# preamp.net
KiCad netlist of a schematic drawn in EAGLE
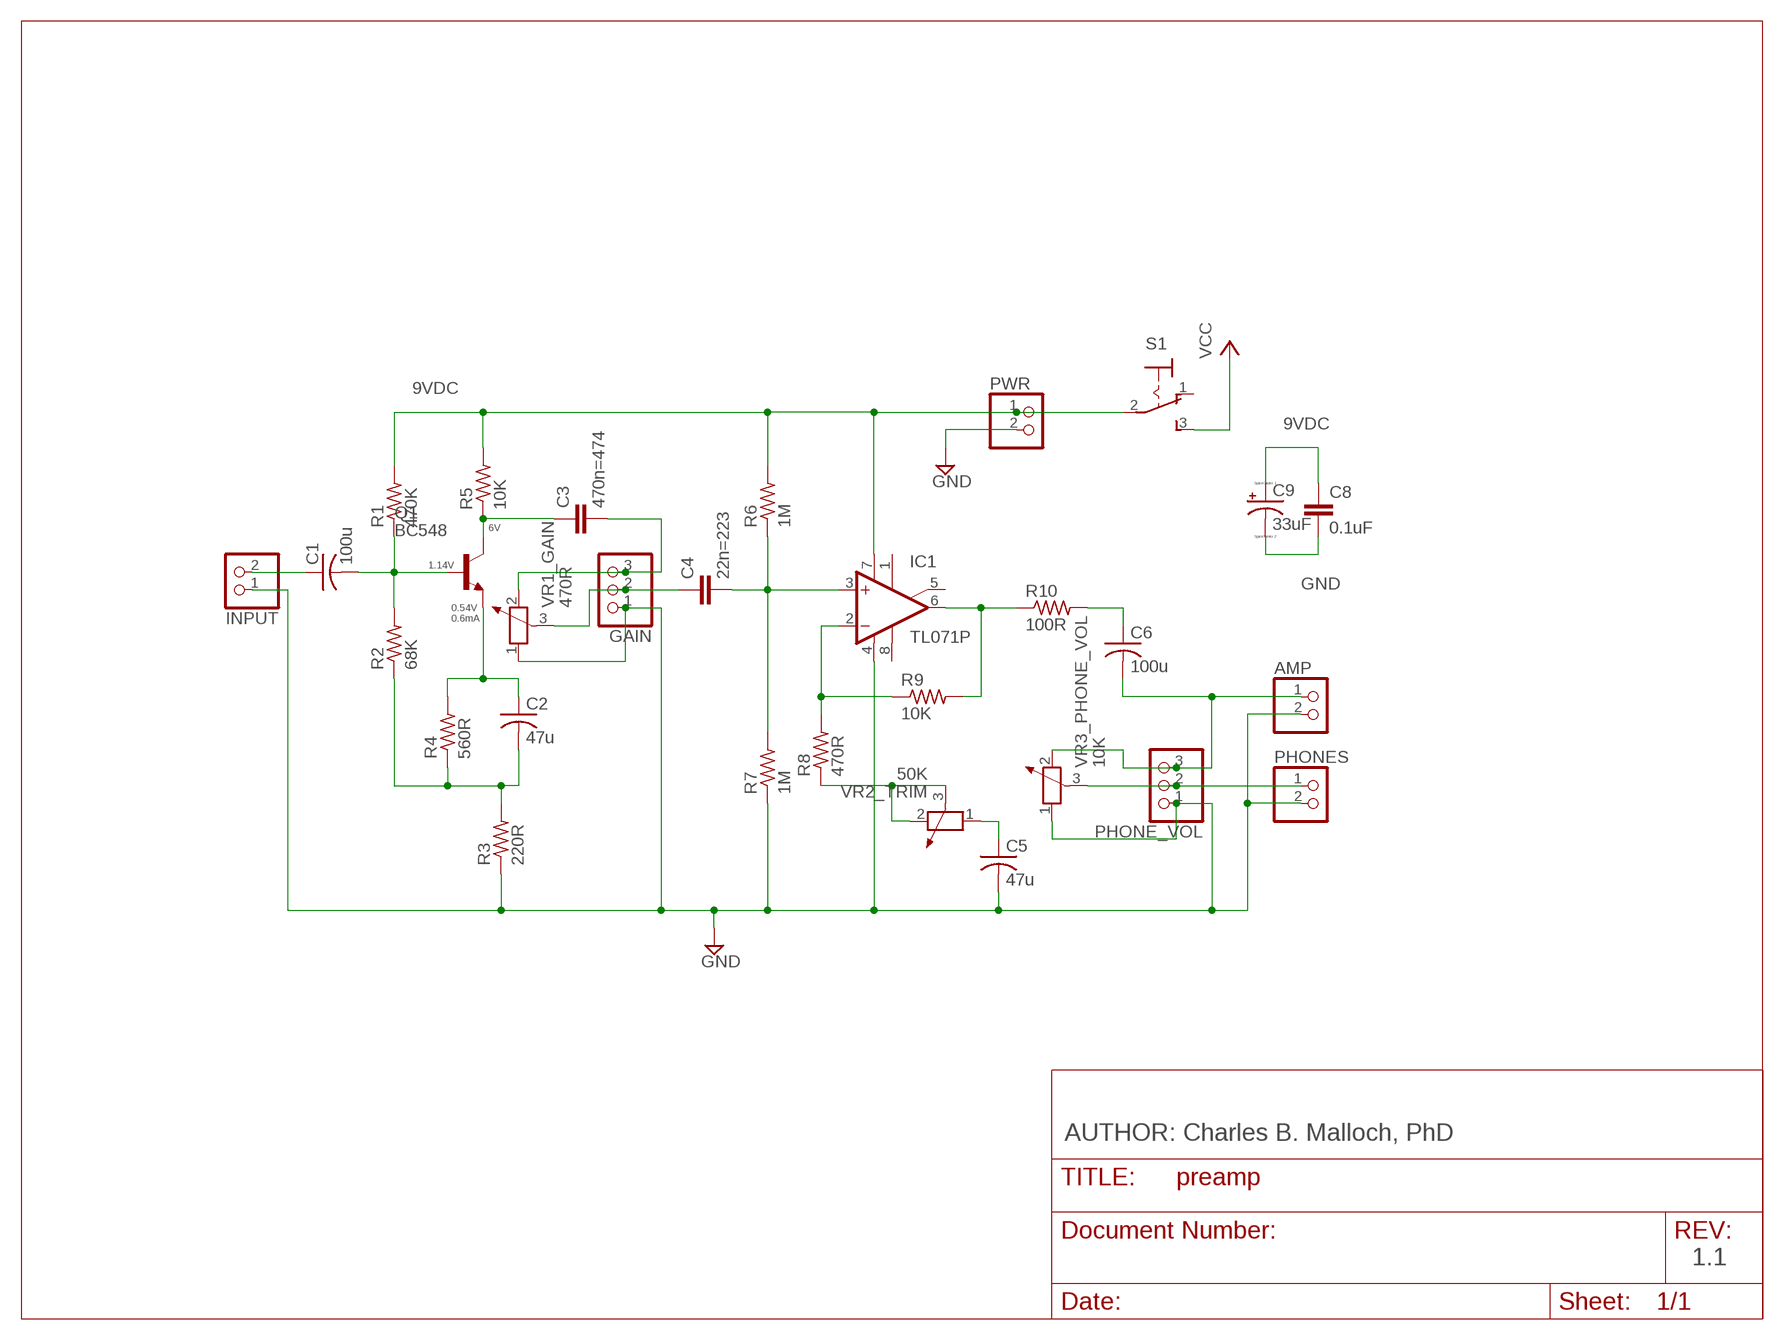
[diagram p0: schematic, sheet 1]

(export (version "E")
  (design (tool "Eeschema 10.0.6"))
  (components
    (comp (ref "AMP")
      (value "PINHD-1X2")
      (footprint "eagle-import:1X02")
      (libsource (lib "eagle-import") (part "PINHD-1X2"))
    )
    (comp (ref "C1")
      (value "100u")
      (footprint "eagle-import:C025-040X050")
      (libsource (lib "eagle-import") (part "C-US025-040X050"))
    )
    (comp (ref "C2")
      (value "47u")
      (footprint "eagle-import:C025-040X050")
      (libsource (lib "eagle-import") (part "C-US025-040X050"))
    )
    (comp (ref "C3")
      (value "470n=474")
      (footprint "eagle-import:C025-060X050")
      (libsource (lib "eagle-import") (part "C-EU025-060X050"))
    )
    (comp (ref "C4")
      (value "22n=223")
      (footprint "eagle-import:C025-060X050")
      (libsource (lib "eagle-import") (part "C-EU025-060X050"))
    )
    (comp (ref "C5")
      (value "47u")
      (footprint "eagle-import:C025-040X050")
      (libsource (lib "eagle-import") (part "C-US025-040X050"))
    )
    (comp (ref "C6")
      (value "100u")
      (footprint "eagle-import:C025-040X050")
      (libsource (lib "eagle-import") (part "C-US025-040X050"))
    )
    (comp (ref "C8")
      (value "0.1uF")
      (footprint "eagle-import:C025-030X050")
      (libsource (lib "eagle-import") (part "resistor_348_C-EU025-030X050"))
    )
    (comp (ref "C9")
      (value "33uF")
      (footprint "eagle-import:E5-6")
      (libsource (lib "eagle-import") (part "CPOL-USE5-6"))
    )
    (comp (ref "GAIN")
      (value "PINHD-1X3")
      (footprint "eagle-import:1X03")
      (libsource (lib "eagle-import") (part "PINHD-1X3"))
    )
    (comp (ref "IC1")
      (value "TL071P")
      (footprint "eagle-import:DIL08")
      (libsource (lib "eagle-import") (part "TL071P"))
    )
    (comp (ref "INPUT")
      (value "PINHD-1X2")
      (footprint "eagle-import:1X02")
      (libsource (lib "eagle-import") (part "PINHD-1X2"))
    )
    (comp (ref "PHONES")
      (value "PINHD-1X2")
      (footprint "eagle-import:1X02")
      (libsource (lib "eagle-import") (part "PINHD-1X2"))
    )
    (comp (ref "PHONE_VOL")
      (value "PINHD-1X3")
      (footprint "eagle-import:1X03")
      (libsource (lib "eagle-import") (part "PINHD-1X3"))
    )
    (comp (ref "PWR")
      (value "PINHD-1X2")
      (footprint "eagle-import:1X02")
      (libsource (lib "eagle-import") (part "PINHD-1X2"))
    )
    (comp (ref "Q1")
      (value "BC548")
      (footprint "eagle-import:TO92-EBC")
      (libsource (lib "eagle-import") (part "BC548"))
    )
    (comp (ref "R1")
      (value "470K")
      (footprint "eagle-import:0204_7")
      (libsource (lib "eagle-import") (part "R-US_0204/7"))
    )
    (comp (ref "R2")
      (value "68K")
      (footprint "eagle-import:0204_7")
      (libsource (lib "eagle-import") (part "R-US_0204/7"))
    )
    (comp (ref "R3")
      (value "220R")
      (footprint "eagle-import:0204_7")
      (libsource (lib "eagle-import") (part "R-US_0204/7"))
    )
    (comp (ref "R4")
      (value "560R")
      (footprint "eagle-import:0204_7")
      (libsource (lib "eagle-import") (part "R-US_0204/7"))
    )
    (comp (ref "R5")
      (value "10K")
      (footprint "eagle-import:0204_7")
      (libsource (lib "eagle-import") (part "R-US_0204/7"))
    )
    (comp (ref "R6")
      (value "1M")
      (footprint "eagle-import:0204_7")
      (libsource (lib "eagle-import") (part "R-US_0204/7"))
    )
    (comp (ref "R7")
      (value "1M")
      (footprint "eagle-import:0204_7")
      (libsource (lib "eagle-import") (part "R-US_0204/7"))
    )
    (comp (ref "R8")
      (value "470R")
      (footprint "eagle-import:0204_7")
      (libsource (lib "eagle-import") (part "R-US_0204/7"))
    )
    (comp (ref "R9")
      (value "10K")
      (footprint "eagle-import:0204_7")
      (libsource (lib "eagle-import") (part "R-US_0204/7"))
    )
    (comp (ref "R10")
      (value "100R")
      (footprint "eagle-import:0204_7")
      (libsource (lib "eagle-import") (part "R-US_0204/7"))
    )
    (comp (ref "S1")
      (value "320-916")
      (footprint "eagle-import:320-916")
      (libsource (lib "eagle-import") (part "320-916"))
    )
    (comp (ref "VR1_GAIN")
      (value "470R")
      (footprint "eagle-import:PT-10")
      (libsource (lib "eagle-import") (part "POTENTIOMETER_PT-10"))
    )
    (comp (ref "VR2_TRIM")
      (value "50K")
      (footprint "eagle-import:PT-10")
      (libsource (lib "eagle-import") (part "POTENTIOMETER_PT-10"))
    )
    (comp (ref "VR3_PHONE_VOL")
      (value "10K")
      (footprint "eagle-import:PT-10")
      (libsource (lib "eagle-import") (part "POTENTIOMETER_PT-10"))
    )
  )
  (nets
    (net (code "1") (name "/9VDC") (class "Default")
      (node (ref "C8") (pin "1") (pinfunction "1_1") (pintype "passive"))
      (node (ref "C9") (pin "+") (pinfunction "+_+") (pintype "passive"))
      (node (ref "IC1") (pin "7") (pinfunction "V+_7") (pintype "power_in"))
      (node (ref "PWR") (pin "1") (pinfunction "1_1") (pintype "passive"))
      (node (ref "R1") (pin "2") (pinfunction "2_2") (pintype "passive"))
      (node (ref "R5") (pin "2") (pinfunction "2_2") (pintype "passive"))
      (node (ref "R6") (pin "2") (pinfunction "2_2") (pintype "passive"))
      (node (ref "S1") (pin "2") (pinfunction "P_2") (pintype "passive"))
    )
    (net (code "2") (name "GND") (class "Default")
      (node (ref "AMP") (pin "2") (pinfunction "2_2") (pintype "passive"))
      (node (ref "C5") (pin "2") (pinfunction "2_2") (pintype "passive"))
      (node (ref "C8") (pin "2") (pinfunction "2_2") (pintype "passive"))
      (node (ref "C9") (pin "-") (pinfunction "-_-") (pintype "passive"))
      (node (ref "GAIN") (pin "1") (pinfunction "1_1") (pintype "passive"))
      (node (ref "IC1") (pin "4") (pinfunction "V-_4") (pintype "power_in"))
      (node (ref "INPUT") (pin "1") (pinfunction "1_1") (pintype "passive"))
      (node (ref "PHONES") (pin "2") (pinfunction "2_2") (pintype "passive"))
      (node (ref "PHONE_VOL") (pin "1") (pinfunction "1_1") (pintype "passive"))
      (node (ref "PWR") (pin "2") (pinfunction "2_2") (pintype "passive"))
      (node (ref "R3") (pin "1") (pinfunction "1_1") (pintype "passive"))
      (node (ref "R7") (pin "1") (pinfunction "1_1") (pintype "passive"))
      (node (ref "VR1_GAIN") (pin "1") (pinfunction "1_1") (pintype "passive"))
      (node (ref "VR3_PHONE_VOL") (pin "1") (pinfunction "1_1") (pintype "passive"))
    )
    (net (code "3") (name "Net-(AMP-Pad1)") (class "Default")
      (node (ref "AMP") (pin "1") (pinfunction "1_1") (pintype "passive"))
      (node (ref "C6") (pin "2") (pinfunction "2_2") (pintype "passive"))
      (node (ref "PHONE_VOL") (pin "3") (pinfunction "3_3") (pintype "passive"))
      (node (ref "VR3_PHONE_VOL") (pin "2") (pinfunction "2_2") (pintype "passive"))
    )
    (net (code "4") (name "Net-(C1-Pad1)") (class "Default")
      (node (ref "C1") (pin "1") (pinfunction "1_1") (pintype "passive"))
      (node (ref "INPUT") (pin "2") (pinfunction "2_2") (pintype "passive"))
    )
    (net (code "5") (name "Net-(C1-Pad2)") (class "Default")
      (node (ref "C1") (pin "2") (pinfunction "2_2") (pintype "passive"))
      (node (ref "Q1") (pin "B") (pinfunction "B_B") (pintype "passive"))
      (node (ref "R1") (pin "1") (pinfunction "1_1") (pintype "passive"))
      (node (ref "R2") (pin "2") (pinfunction "2_2") (pintype "passive"))
    )
    (net (code "6") (name "Net-(C2-Pad1)") (class "Default")
      (node (ref "C2") (pin "1") (pinfunction "1_1") (pintype "passive"))
      (node (ref "Q1") (pin "E") (pinfunction "E_E") (pintype "passive"))
      (node (ref "R4") (pin "2") (pinfunction "2_2") (pintype "passive"))
    )
    (net (code "7") (name "Net-(C2-Pad2)") (class "Default")
      (node (ref "C2") (pin "2") (pinfunction "2_2") (pintype "passive"))
      (node (ref "R2") (pin "1") (pinfunction "1_1") (pintype "passive"))
      (node (ref "R3") (pin "2") (pinfunction "2_2") (pintype "passive"))
      (node (ref "R4") (pin "1") (pinfunction "1_1") (pintype "passive"))
    )
    (net (code "8") (name "Net-(C3-Pad1)") (class "Default")
      (node (ref "C3") (pin "1") (pinfunction "1_1") (pintype "passive"))
      (node (ref "Q1") (pin "C") (pinfunction "C_C") (pintype "passive"))
      (node (ref "R5") (pin "1") (pinfunction "1_1") (pintype "passive"))
    )
    (net (code "9") (name "Net-(C3-Pad2)") (class "Default")
      (node (ref "C3") (pin "2") (pinfunction "2_2") (pintype "passive"))
      (node (ref "GAIN") (pin "3") (pinfunction "3_3") (pintype "passive"))
      (node (ref "VR1_GAIN") (pin "2") (pinfunction "2_2") (pintype "passive"))
    )
    (net (code "10") (name "Net-(C4-Pad1)") (class "Default")
      (node (ref "C4") (pin "1") (pinfunction "1_1") (pintype "passive"))
      (node (ref "GAIN") (pin "2") (pinfunction "2_2") (pintype "passive"))
      (node (ref "VR1_GAIN") (pin "3") (pinfunction "3_3") (pintype "passive"))
    )
    (net (code "11") (name "Net-(C5-Pad1)") (class "Default")
      (node (ref "C5") (pin "1") (pinfunction "1_1") (pintype "passive"))
      (node (ref "VR2_TRIM") (pin "1") (pinfunction "1_1") (pintype "passive"))
    )
    (net (code "12") (name "Net-(C6-Pad1)") (class "Default")
      (node (ref "C6") (pin "1") (pinfunction "1_1") (pintype "passive"))
      (node (ref "R10") (pin "2") (pinfunction "2_2") (pintype "passive"))
    )
    (net (code "13") (name "Net-(IC1-+IN)") (class "Default")
      (node (ref "C4") (pin "2") (pinfunction "2_2") (pintype "passive"))
      (node (ref "IC1") (pin "3") (pinfunction "+IN_3") (pintype "input"))
      (node (ref "R6") (pin "1") (pinfunction "1_1") (pintype "passive"))
      (node (ref "R7") (pin "2") (pinfunction "2_2") (pintype "passive"))
    )
    (net (code "14") (name "Net-(IC1--IN)") (class "Default")
      (node (ref "IC1") (pin "2") (pinfunction "-IN_2") (pintype "input"))
      (node (ref "R8") (pin "2") (pinfunction "2_2") (pintype "passive"))
      (node (ref "R9") (pin "1") (pinfunction "1_1") (pintype "passive"))
    )
    (net (code "15") (name "Net-(IC1-OUT)") (class "Default")
      (node (ref "IC1") (pin "6") (pinfunction "OUT_6") (pintype "output"))
      (node (ref "R10") (pin "1") (pinfunction "1_1") (pintype "passive"))
      (node (ref "R9") (pin "2") (pinfunction "2_2") (pintype "passive"))
    )
    (net (code "16") (name "Net-(PHONES-Pad1)") (class "Default")
      (node (ref "PHONES") (pin "1") (pinfunction "1_1") (pintype "passive"))
      (node (ref "PHONE_VOL") (pin "2") (pinfunction "2_2") (pintype "passive"))
      (node (ref "VR3_PHONE_VOL") (pin "3") (pinfunction "3_3") (pintype "passive"))
    )
    (net (code "17") (name "Net-(R8-Pad1)") (class "Default")
      (node (ref "R8") (pin "1") (pinfunction "1_1") (pintype "passive"))
      (node (ref "VR2_TRIM") (pin "2") (pinfunction "2_2") (pintype "passive"))
      (node (ref "VR2_TRIM") (pin "3") (pinfunction "3_3") (pintype "passive"))
    )
    (net (code "18") (name "VCC") (class "Default")
      (node (ref "S1") (pin "3") (pinfunction "S_3") (pintype "passive"))
    )
    (net (code "19") (name "unconnected-(IC1-ON1-Pad1)") (class "Default")
      (node (ref "IC1") (pin "1") (pinfunction "ON1_1") (pintype "passive"))
    )
    (net (code "20") (name "unconnected-(IC1-ON2-Pad5)") (class "Default")
      (node (ref "IC1") (pin "5") (pinfunction "ON2_5") (pintype "passive"))
    )
    (net (code "21") (name "unconnected-(IC1-OPT-Pad8)") (class "Default")
      (node (ref "IC1") (pin "8") (pinfunction "OPT_8") (pintype "passive"))
    )
    (net (code "22") (name "unconnected-(S1-O-Pad1)") (class "Default")
      (node (ref "S1") (pin "1") (pinfunction "O_1") (pintype "passive"))
    )
  )
)
